# TQFP32Adapter.net
KiCad netlist of a schematic drawn in EAGLE
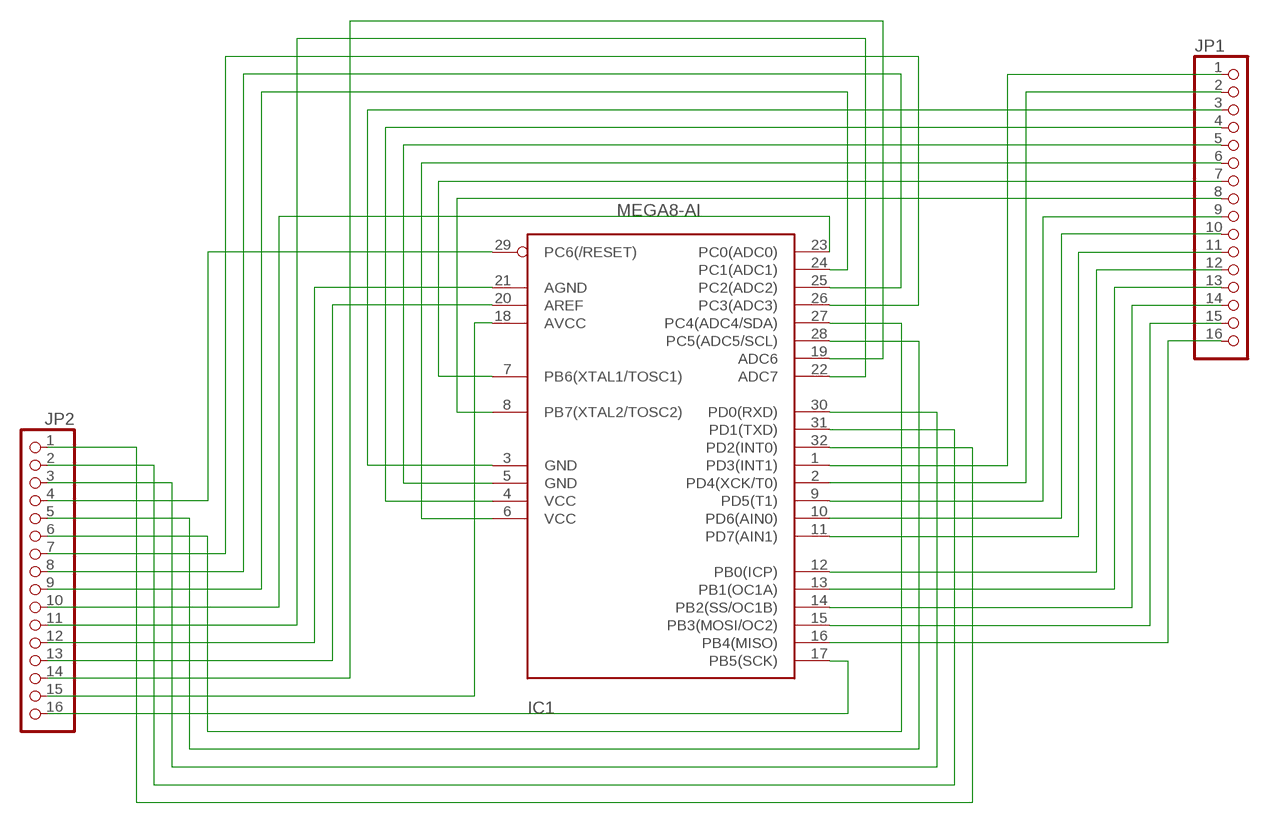
[diagram p0: schematic, sheet 1]

(export (version "E")
  (design (tool "Eeschema 10.0.6"))
  (components
    (comp (ref "IC1")
      (value "MEGA8-AI")
      (footprint "eagle-import:TQFP32-08")
      (libsource (lib "eagle-import") (part "MEGA8-AI"))
    )
    (comp (ref "JP1")
      (value "PINHD-1X16")
      (footprint "eagle-import:1X16")
      (libsource (lib "eagle-import") (part "PINHD-1X16"))
    )
    (comp (ref "JP2")
      (value "PINHD-1X16")
      (footprint "eagle-import:1X16")
      (libsource (lib "eagle-import") (part "PINHD-1X16"))
    )
  )
  (nets
    (net (code "1") (name "Net-(IC1-ADC6)") (class "Default")
      (node (ref "IC1") (pin "19") (pinfunction "ADC6_19") (pintype "bidirectional"))
      (node (ref "JP2") (pin "14") (pinfunction "14_14") (pintype "passive"))
    )
    (net (code "2") (name "Net-(IC1-ADC7)") (class "Default")
      (node (ref "IC1") (pin "22") (pinfunction "ADC7_22") (pintype "bidirectional"))
      (node (ref "JP2") (pin "11") (pinfunction "11_11") (pintype "passive"))
    )
    (net (code "3") (name "Net-(IC1-AGND)") (class "Default")
      (node (ref "IC1") (pin "21") (pinfunction "AGND_21") (pintype "bidirectional"))
      (node (ref "JP2") (pin "12") (pinfunction "12_12") (pintype "passive"))
    )
    (net (code "4") (name "Net-(IC1-AREF)") (class "Default")
      (node (ref "IC1") (pin "20") (pinfunction "AREF_20") (pintype "bidirectional"))
      (node (ref "JP2") (pin "13") (pinfunction "13_13") (pintype "passive"))
    )
    (net (code "5") (name "Net-(IC1-AVCC)") (class "Default")
      (node (ref "IC1") (pin "18") (pinfunction "AVCC_18") (pintype "bidirectional"))
      (node (ref "JP2") (pin "15") (pinfunction "15_15") (pintype "passive"))
    )
    (net (code "6") (name "Net-(IC1-GND-Pad3)") (class "Default")
      (node (ref "IC1") (pin "3") (pinfunction "GND_3") (pintype "bidirectional"))
      (node (ref "JP1") (pin "3") (pinfunction "3_3") (pintype "passive"))
    )
    (net (code "7") (name "Net-(IC1-GND-Pad5)") (class "Default")
      (node (ref "IC1") (pin "5") (pinfunction "GND_5") (pintype "bidirectional"))
      (node (ref "JP1") (pin "5") (pinfunction "5_5") (pintype "passive"))
    )
    (net (code "8") (name "Net-(IC1-PB0(ICP))") (class "Default")
      (node (ref "IC1") (pin "12") (pinfunction "PB0(ICP)_12") (pintype "bidirectional"))
      (node (ref "JP1") (pin "12") (pinfunction "12_12") (pintype "passive"))
    )
    (net (code "9") (name "Net-(IC1-PB1(OC1A))") (class "Default")
      (node (ref "IC1") (pin "13") (pinfunction "PB1(OC1A)_13") (pintype "bidirectional"))
      (node (ref "JP1") (pin "13") (pinfunction "13_13") (pintype "passive"))
    )
    (net (code "10") (name "Net-(IC1-PB2(SS{slash}OC1B))") (class "Default")
      (node (ref "IC1") (pin "14") (pinfunction "PB2(SS/OC1B)_14") (pintype "bidirectional"))
      (node (ref "JP1") (pin "14") (pinfunction "14_14") (pintype "passive"))
    )
    (net (code "11") (name "Net-(IC1-PB3(MOSI{slash}OC2))") (class "Default")
      (node (ref "IC1") (pin "15") (pinfunction "PB3(MOSI/OC2)_15") (pintype "bidirectional"))
      (node (ref "JP1") (pin "15") (pinfunction "15_15") (pintype "passive"))
    )
    (net (code "12") (name "Net-(IC1-PB4(MISO))") (class "Default")
      (node (ref "IC1") (pin "16") (pinfunction "PB4(MISO)_16") (pintype "bidirectional"))
      (node (ref "JP1") (pin "16") (pinfunction "16_16") (pintype "passive"))
    )
    (net (code "13") (name "Net-(IC1-PB5(SCK))") (class "Default")
      (node (ref "IC1") (pin "17") (pinfunction "PB5(SCK)_17") (pintype "bidirectional"))
      (node (ref "JP2") (pin "16") (pinfunction "16_16") (pintype "passive"))
    )
    (net (code "14") (name "Net-(IC1-PB6(XTAL1{slash}TOSC1))") (class "Default")
      (node (ref "IC1") (pin "7") (pinfunction "PB6(XTAL1/TOSC1)_7") (pintype "bidirectional"))
      (node (ref "JP1") (pin "7") (pinfunction "7_7") (pintype "passive"))
    )
    (net (code "15") (name "Net-(IC1-PB7(XTAL2{slash}TOSC2))") (class "Default")
      (node (ref "IC1") (pin "8") (pinfunction "PB7(XTAL2/TOSC2)_8") (pintype "bidirectional"))
      (node (ref "JP1") (pin "8") (pinfunction "8_8") (pintype "passive"))
    )
    (net (code "16") (name "Net-(IC1-PC0(ADC0))") (class "Default")
      (node (ref "IC1") (pin "23") (pinfunction "PC0(ADC0)_23") (pintype "bidirectional"))
      (node (ref "JP2") (pin "10") (pinfunction "10_10") (pintype "passive"))
    )
    (net (code "17") (name "Net-(IC1-PC1(ADC1))") (class "Default")
      (node (ref "IC1") (pin "24") (pinfunction "PC1(ADC1)_24") (pintype "bidirectional"))
      (node (ref "JP2") (pin "9") (pinfunction "9_9") (pintype "passive"))
    )
    (net (code "18") (name "Net-(IC1-PC2(ADC2))") (class "Default")
      (node (ref "IC1") (pin "25") (pinfunction "PC2(ADC2)_25") (pintype "bidirectional"))
      (node (ref "JP2") (pin "8") (pinfunction "8_8") (pintype "passive"))
    )
    (net (code "19") (name "Net-(IC1-PC3(ADC3))") (class "Default")
      (node (ref "IC1") (pin "26") (pinfunction "PC3(ADC3)_26") (pintype "bidirectional"))
      (node (ref "JP2") (pin "7") (pinfunction "7_7") (pintype "passive"))
    )
    (net (code "20") (name "Net-(IC1-PC4(ADC4{slash}SDA))") (class "Default")
      (node (ref "IC1") (pin "27") (pinfunction "PC4(ADC4/SDA)_27") (pintype "bidirectional"))
      (node (ref "JP2") (pin "6") (pinfunction "6_6") (pintype "passive"))
    )
    (net (code "21") (name "Net-(IC1-PC5(ADC5{slash}SCL))") (class "Default")
      (node (ref "IC1") (pin "28") (pinfunction "PC5(ADC5/SCL)_28") (pintype "bidirectional"))
      (node (ref "JP2") (pin "5") (pinfunction "5_5") (pintype "passive"))
    )
    (net (code "22") (name "Net-(IC1-PC6({slash}RESET))") (class "Default")
      (node (ref "IC1") (pin "29") (pinfunction "PC6(/RESET)_29") (pintype "bidirectional"))
      (node (ref "JP2") (pin "4") (pinfunction "4_4") (pintype "passive"))
    )
    (net (code "23") (name "Net-(IC1-PD0(RXD))") (class "Default")
      (node (ref "IC1") (pin "30") (pinfunction "PD0(RXD)_30") (pintype "bidirectional"))
      (node (ref "JP2") (pin "3") (pinfunction "3_3") (pintype "passive"))
    )
    (net (code "24") (name "Net-(IC1-PD1(TXD))") (class "Default")
      (node (ref "IC1") (pin "31") (pinfunction "PD1(TXD)_31") (pintype "bidirectional"))
      (node (ref "JP2") (pin "2") (pinfunction "2_2") (pintype "passive"))
    )
    (net (code "25") (name "Net-(IC1-PD2(INT0))") (class "Default")
      (node (ref "IC1") (pin "32") (pinfunction "PD2(INT0)_32") (pintype "bidirectional"))
      (node (ref "JP2") (pin "1") (pinfunction "1_1") (pintype "passive"))
    )
    (net (code "26") (name "Net-(IC1-PD3(INT1))") (class "Default")
      (node (ref "IC1") (pin "1") (pinfunction "PD3(INT1)_1") (pintype "bidirectional"))
      (node (ref "JP1") (pin "1") (pinfunction "1_1") (pintype "passive"))
    )
    (net (code "27") (name "Net-(IC1-PD4(XCK{slash}T0))") (class "Default")
      (node (ref "IC1") (pin "2") (pinfunction "PD4(XCK/T0)_2") (pintype "bidirectional"))
      (node (ref "JP1") (pin "2") (pinfunction "2_2") (pintype "passive"))
    )
    (net (code "28") (name "Net-(IC1-PD5(T1))") (class "Default")
      (node (ref "IC1") (pin "9") (pinfunction "PD5(T1)_9") (pintype "bidirectional"))
      (node (ref "JP1") (pin "9") (pinfunction "9_9") (pintype "passive"))
    )
    (net (code "29") (name "Net-(IC1-PD6(AIN0))") (class "Default")
      (node (ref "IC1") (pin "10") (pinfunction "PD6(AIN0)_10") (pintype "bidirectional"))
      (node (ref "JP1") (pin "10") (pinfunction "10_10") (pintype "passive"))
    )
    (net (code "30") (name "Net-(IC1-PD7(AIN1))") (class "Default")
      (node (ref "IC1") (pin "11") (pinfunction "PD7(AIN1)_11") (pintype "bidirectional"))
      (node (ref "JP1") (pin "11") (pinfunction "11_11") (pintype "passive"))
    )
    (net (code "31") (name "Net-(IC1-VCC-Pad4)") (class "Default")
      (node (ref "IC1") (pin "4") (pinfunction "VCC_4") (pintype "bidirectional"))
      (node (ref "JP1") (pin "4") (pinfunction "4_4") (pintype "passive"))
    )
    (net (code "32") (name "Net-(IC1-VCC-Pad6)") (class "Default")
      (node (ref "IC1") (pin "6") (pinfunction "VCC_6") (pintype "bidirectional"))
      (node (ref "JP1") (pin "6") (pinfunction "6_6") (pintype "passive"))
    )
  )
)
